# usbuartLayout.net
KiCad netlist of a schematic drawn in EAGLE
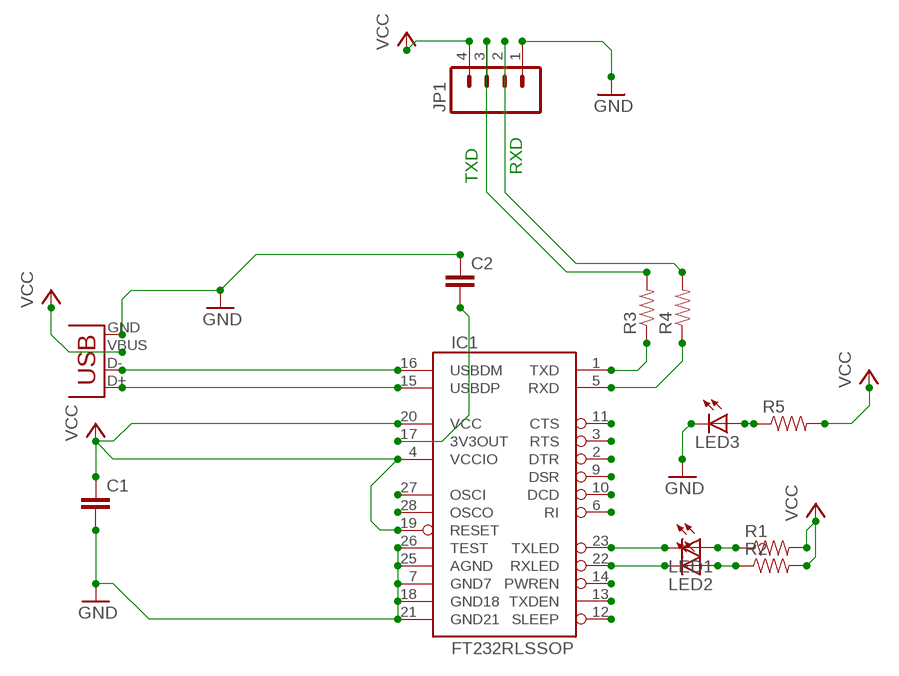
[diagram p0: schematic, sheet 1]

(export (version "E")
  (design (tool "Eeschema 10.0.6"))
  (components
    (comp (ref "C1")
      (value "CAP1206")
      (footprint "eagle-import:1206")
      (libsource (lib "eagle-import") (part "CAP1206"))
    )
    (comp (ref "C2")
      (value "CAP1206")
      (footprint "eagle-import:1206")
      (libsource (lib "eagle-import") (part "CAP1206"))
    )
    (comp (ref "IC1")
      (value "FT232RLSSOP")
      (footprint "eagle-import:SSOP28DB")
      (libsource (lib "eagle-import") (part "FT232RLSSOP"))
    )
    (comp (ref "JP1")
      (value "M04SMD")
      (footprint "eagle-import:1X04-SMD")
      (libsource (lib "eagle-import") (part "M04SMD"))
    )
    (comp (ref "LED1")
      (value "LEDCHIPLED_1206")
      (footprint "eagle-import:CHIPLED_1206")
      (libsource (lib "eagle-import") (part "LEDCHIPLED_1206"))
    )
    (comp (ref "LED2")
      (value "LEDCHIPLED_1206")
      (footprint "eagle-import:CHIPLED_1206")
      (libsource (lib "eagle-import") (part "LEDCHIPLED_1206"))
    )
    (comp (ref "LED3")
      (value "LEDCHIPLED_1206")
      (footprint "eagle-import:CHIPLED_1206")
      (libsource (lib "eagle-import") (part "LEDCHIPLED_1206"))
    )
    (comp (ref "R1")
      (value "RESISTOR1206")
      (footprint "eagle-import:1206")
      (libsource (lib "eagle-import") (part "RESISTOR1206"))
    )
    (comp (ref "R2")
      (value "RESISTOR1206")
      (footprint "eagle-import:1206")
      (libsource (lib "eagle-import") (part "RESISTOR1206"))
    )
    (comp (ref "R3")
      (value "RESISTOR1206")
      (footprint "eagle-import:1206")
      (libsource (lib "eagle-import") (part "RESISTOR1206"))
    )
    (comp (ref "R4")
      (value "RESISTOR1206")
      (footprint "eagle-import:1206")
      (libsource (lib "eagle-import") (part "RESISTOR1206"))
    )
    (comp (ref "R5")
      (value "RESISTOR1206")
      (footprint "eagle-import:1206")
      (libsource (lib "eagle-import") (part "RESISTOR1206"))
    )
    (comp (ref "X1")
      (value "USB-SMD-NS")
      (footprint "eagle-import:USB-MINIB-NOSTOP")
      (libsource (lib "eagle-import") (part "USB-SMD-NS"))
    )
  )
  (nets
    (net (code "1") (name "GND") (class "Default")
      (node (ref "C1") (pin "2") (pinfunction "2_2") (pintype "passive"))
      (node (ref "C2") (pin "1") (pinfunction "1_1") (pintype "passive"))
      (node (ref "IC1") (pin "18") (pinfunction "GND18_18") (pintype "power_in"))
      (node (ref "IC1") (pin "21") (pinfunction "GND21_21") (pintype "power_in"))
      (node (ref "IC1") (pin "25") (pinfunction "AGND_25") (pintype "power_in"))
      (node (ref "IC1") (pin "26") (pinfunction "TEST_26") (pintype "input"))
      (node (ref "IC1") (pin "7") (pinfunction "GND7_7") (pintype "power_in"))
      (node (ref "JP1") (pin "1") (pinfunction "1_1") (pintype "passive"))
      (node (ref "LED3") (pin "C") (pinfunction "C_C") (pintype "passive"))
      (node (ref "X1") (pin "GND") (pinfunction "GND_GND") (pintype "bidirectional"))
    )
    (net (code "2") (name "Net-(IC1-3V3OUT)") (class "Default")
      (node (ref "C2") (pin "2") (pinfunction "2_2") (pintype "passive"))
      (node (ref "IC1") (pin "17") (pinfunction "3V3OUT_17") (pintype "output"))
    )
    (net (code "3") (name "Net-(IC1-RXD)") (class "Default")
      (node (ref "IC1") (pin "5") (pinfunction "RXD_5") (pintype "input"))
      (node (ref "R4") (pin "1") (pinfunction "1_1") (pintype "passive"))
    )
    (net (code "4") (name "Net-(IC1-RXLED)") (class "Default")
      (node (ref "IC1") (pin "22") (pinfunction "RXLED_22") (pintype "input"))
      (node (ref "LED2") (pin "C") (pinfunction "C_C") (pintype "passive"))
    )
    (net (code "5") (name "Net-(IC1-TXD)") (class "Default")
      (node (ref "IC1") (pin "1") (pinfunction "TXD_1") (pintype "output"))
      (node (ref "R3") (pin "1") (pinfunction "1_1") (pintype "passive"))
    )
    (net (code "6") (name "Net-(IC1-TXLED)") (class "Default")
      (node (ref "IC1") (pin "23") (pinfunction "TXLED_23") (pintype "input"))
      (node (ref "LED1") (pin "C") (pinfunction "C_C") (pintype "passive"))
    )
    (net (code "7") (name "Net-(IC1-USBDM)") (class "Default")
      (node (ref "IC1") (pin "16") (pinfunction "USBDM_16") (pintype "bidirectional"))
      (node (ref "X1") (pin "D-") (pinfunction "D-_D-") (pintype "bidirectional"))
    )
    (net (code "8") (name "Net-(IC1-USBDP)") (class "Default")
      (node (ref "IC1") (pin "15") (pinfunction "USBDP_15") (pintype "bidirectional"))
      (node (ref "X1") (pin "D+") (pinfunction "D+_D+") (pintype "bidirectional"))
    )
    (net (code "9") (name "Net-(JP1-Pad2)") (class "Default")
      (node (ref "JP1") (pin "2") (pinfunction "2_2") (pintype "passive"))
      (node (ref "R4") (pin "2") (pinfunction "2_2") (pintype "passive"))
    )
    (net (code "10") (name "Net-(JP1-Pad3)") (class "Default")
      (node (ref "JP1") (pin "3") (pinfunction "3_3") (pintype "passive"))
      (node (ref "R3") (pin "2") (pinfunction "2_2") (pintype "passive"))
    )
    (net (code "11") (name "Net-(LED1-PadA)") (class "Default")
      (node (ref "LED1") (pin "A") (pinfunction "A_A") (pintype "passive"))
      (node (ref "R1") (pin "1") (pinfunction "1_1") (pintype "passive"))
    )
    (net (code "12") (name "Net-(LED2-PadA)") (class "Default")
      (node (ref "LED2") (pin "A") (pinfunction "A_A") (pintype "passive"))
      (node (ref "R2") (pin "1") (pinfunction "1_1") (pintype "passive"))
    )
    (net (code "13") (name "Net-(LED3-PadA)") (class "Default")
      (node (ref "LED3") (pin "A") (pinfunction "A_A") (pintype "passive"))
      (node (ref "R5") (pin "1") (pinfunction "1_1") (pintype "passive"))
    )
    (net (code "14") (name "VCC") (class "Default")
      (node (ref "C1") (pin "1") (pinfunction "1_1") (pintype "passive"))
      (node (ref "IC1") (pin "19") (pinfunction "RESET_19") (pintype "input"))
      (node (ref "IC1") (pin "20") (pinfunction "VCC_20") (pintype "power_in"))
      (node (ref "IC1") (pin "4") (pinfunction "VCCIO_4") (pintype "power_in"))
      (node (ref "JP1") (pin "4") (pinfunction "4_4") (pintype "passive"))
      (node (ref "R1") (pin "2") (pinfunction "2_2") (pintype "passive"))
      (node (ref "R2") (pin "2") (pinfunction "2_2") (pintype "passive"))
      (node (ref "R5") (pin "2") (pinfunction "2_2") (pintype "passive"))
      (node (ref "X1") (pin "VBUS") (pinfunction "VBUS_VBUS") (pintype "bidirectional"))
    )
    (net (code "15") (name "unconnected-(IC1-CTS-Pad11)") (class "Default")
      (node (ref "IC1") (pin "11") (pinfunction "CTS_11") (pintype "input"))
    )
    (net (code "16") (name "unconnected-(IC1-DCD-Pad10)") (class "Default")
      (node (ref "IC1") (pin "10") (pinfunction "DCD_10") (pintype "input"))
    )
    (net (code "17") (name "unconnected-(IC1-DSR-Pad9)") (class "Default")
      (node (ref "IC1") (pin "9") (pinfunction "DSR_9") (pintype "input"))
    )
    (net (code "18") (name "unconnected-(IC1-DTR-Pad2)") (class "Default")
      (node (ref "IC1") (pin "2") (pinfunction "DTR_2") (pintype "output"))
    )
    (net (code "19") (name "unconnected-(IC1-OSCI-Pad27)") (class "Default")
      (node (ref "IC1") (pin "27") (pinfunction "OSCI_27") (pintype "input"))
    )
    (net (code "20") (name "unconnected-(IC1-OSCO-Pad28)") (class "Default")
      (node (ref "IC1") (pin "28") (pinfunction "OSCO_28") (pintype "output"))
    )
    (net (code "21") (name "unconnected-(IC1-PWREN-Pad14)") (class "Default")
      (node (ref "IC1") (pin "14") (pinfunction "PWREN_14") (pintype "input"))
    )
    (net (code "22") (name "unconnected-(IC1-RI-Pad6)") (class "Default")
      (node (ref "IC1") (pin "6") (pinfunction "RI_6") (pintype "input"))
    )
    (net (code "23") (name "unconnected-(IC1-RTS-Pad3)") (class "Default")
      (node (ref "IC1") (pin "3") (pinfunction "RTS_3") (pintype "output"))
    )
    (net (code "24") (name "unconnected-(IC1-SLEEP-Pad12)") (class "Default")
      (node (ref "IC1") (pin "12") (pinfunction "SLEEP_12") (pintype "input"))
    )
    (net (code "25") (name "unconnected-(IC1-TXDEN-Pad13)") (class "Default")
      (node (ref "IC1") (pin "13") (pinfunction "TXDEN_13") (pintype "input"))
    )
  )
)
